# E22_TTL_RS232_v0_1_-20200417.net
KiCad netlist of a schematic drawn in Altium Designer
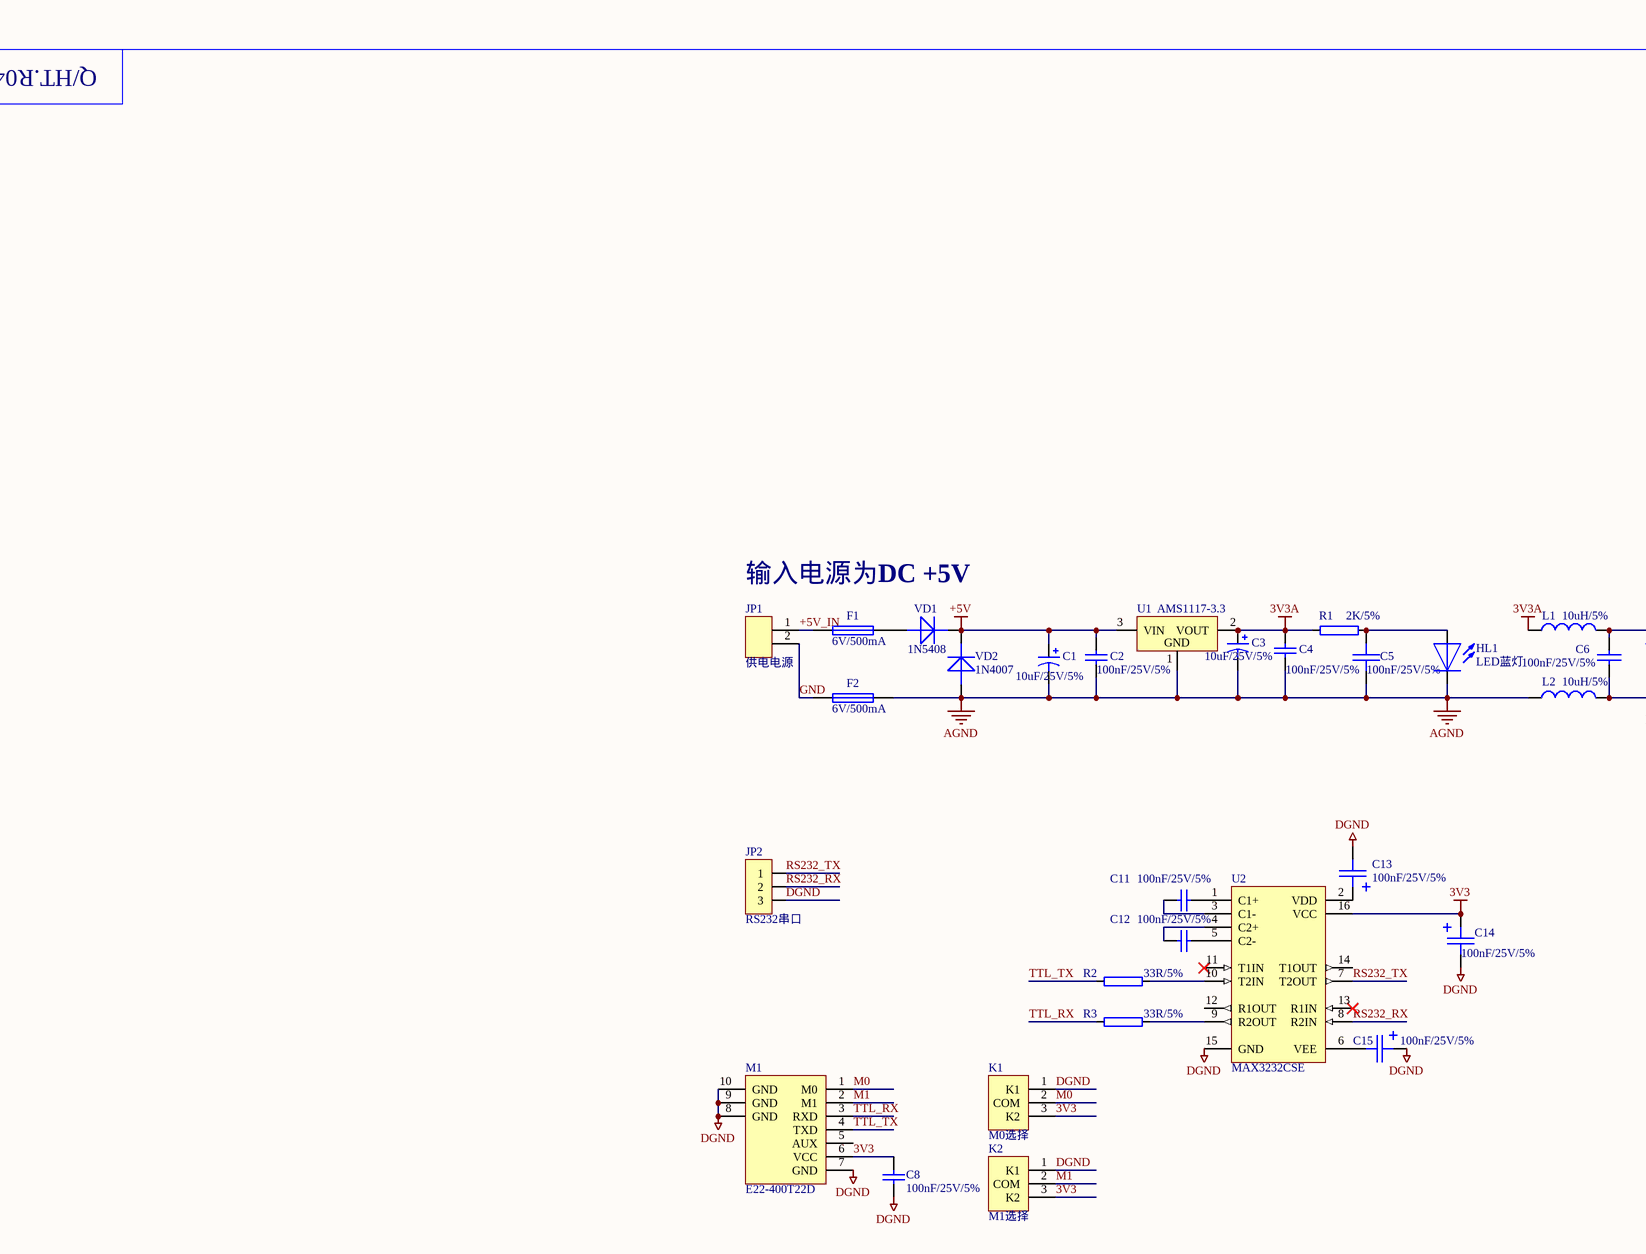
[diagram p0: E22_TTL_RS232(v0.1)-20200417.SchDoc, top left]
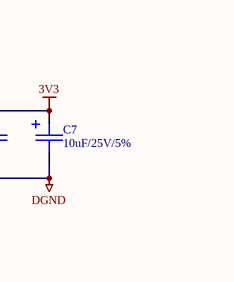
[diagram p1: E22_TTL_RS232(v0.1)-20200417.SchDoc, top right]
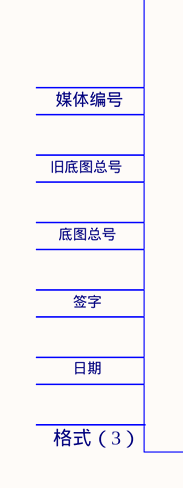
[diagram p2: E22_TTL_RS232(v0.1)-20200417.SchDoc, bottom left]
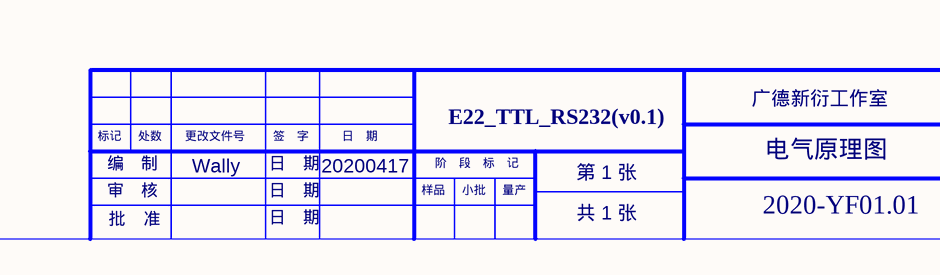
[diagram p3: E22_TTL_RS232(v0.1)-20200417.SchDoc, bottom right]

(export (version "E")
  (design (tool "Eeschema 10.0.6"))
  (components
    (comp (ref "C1")
      (value "10uF/25V/5%")
      (footprint "C1206-1")
      (description "钽电容")
      (fields (field (name "PUBLISHER") "Altium Limited"))
      (libsource (lib "Miscellaneous Devices") (part "Cap Pol1"))
    )
    (comp (ref "C2")
      (value "100nF/25V/5%")
      (footprint "C0603")
      (description "电容")
      (fields (field (name "PUBLISHER") "Altium Limited"))
      (libsource (lib "Miscellaneous Devices") (part "Cap"))
    )
    (comp (ref "C3")
      (value "10uF/25V/5%")
      (footprint "C1206-1")
      (description "钽电容")
      (fields (field (name "PUBLISHER") "Altium Limited"))
      (libsource (lib "Miscellaneous Devices") (part "Cap Pol1"))
    )
    (comp (ref "C4")
      (value "100nF/25V/5%")
      (footprint "C0603")
      (description "电容")
      (fields (field (name "PUBLISHER") "Altium Limited"))
      (libsource (lib "Miscellaneous Devices") (part "Cap"))
    )
    (comp (ref "C5")
      (value "100nF/25V/5%")
      (footprint "C0603")
      (description "电容")
      (libsource (lib "") (part "CAP_1"))
    )
    (comp (ref "C6")
      (value "100nF/25V/5%")
      (footprint "C0603")
      (description "电容")
      (libsource (lib "*") (part "CAP"))
    )
    (comp (ref "C7")
      (value "10uF/25V/5%")
      (footprint "C1206-1")
      (description "钽电容")
      (libsource (lib "*") (part "ELECTRO1"))
    )
    (comp (ref "C8")
      (value "100nF/25V/5%")
      (footprint "C0603")
      (description "电容")
      (libsource (lib "*") (part "CAP-SMD"))
    )
    (comp (ref "C11")
      (value "100nF/25V/5%")
      (footprint "C0603")
      (description "电容")
      (libsource (lib "*") (part "CAP-SMD"))
    )
    (comp (ref "C12")
      (value "100nF/25V/5%")
      (footprint "C0603")
      (description "电容")
      (libsource (lib "*") (part "CAP-SMD"))
    )
    (comp (ref "C13")
      (value "100nF/25V/5%")
      (footprint "C1206-1")
      (description "钽电容")
      (libsource (lib "*") (part "ELECTRO1"))
    )
    (comp (ref "C14")
      (value "100nF/25V/5%")
      (footprint "C1206-1")
      (description "钽电容")
      (libsource (lib "*") (part "ELECTRO1"))
    )
    (comp (ref "C15")
      (value "100nF/25V/5%")
      (footprint "C1206-1")
      (description "钽电容")
      (libsource (lib "*") (part "ELECTRO1"))
    )
    (comp (ref "F1")
      (value "6V/500mA")
      (footprint "F1812")
      (description "自恢复保险丝")
      (libsource (lib "wypPCB_Lib") (part "保险丝"))
    )
    (comp (ref "F2")
      (value "6V/500mA")
      (footprint "F1812")
      (description "自恢复保险丝")
      (libsource (lib "wypPCB_Lib") (part "保险丝"))
    )
    (comp (ref "HL1")
      (value "LED蓝灯")
      (footprint "LED0603")
      (description "发光二极管")
      (libsource (lib "wypPCB_Lib") (part "发光二极管"))
    )
    (comp (ref "JP1")
      (value "供电电源")
      (footprint "XH2.54-LI-2P")
      (description "XH2.54-2P/PH2.0-2P插座")
      (libsource (lib "wypPCB_Lib") (part "XH2.54-2P/PH2.0-2P"))
    )
    (comp (ref "JP2")
      (value "RS232串口")
      (footprint "PH2.0-LI-3P")
      (description "PH2.0-3P直插插座")
      (libsource (lib "wypPCB_Lib") (part "XH2.54-3P/PH2.0-3P"))
    )
    (comp (ref "K1")
      (value "M0选择")
      (footprint "SK-12D07")
      (description "SK-12D07：3脚2档小型拨动开关")
      (libsource (lib "wypPCB_Lib") (part "SK-12D07"))
    )
    (comp (ref "K2")
      (value "M1选择")
      (footprint "SK-12D07")
      (description "SK-12D07：3脚2档小型拨动开关")
      (libsource (lib "wypPCB_Lib") (part "SK-12D07"))
    )
    (comp (ref "L1")
      (value "10uH/5%")
      (footprint "L0603")
      (description "电感")
      (libsource (lib "wypPCB_Lib") (part "电感"))
    )
    (comp (ref "L2")
      (value "10uH/5%")
      (footprint "L0603")
      (description "电感")
      (libsource (lib "wypPCB_Lib") (part "电感"))
    )
    (comp (ref "M1")
      (value "E22-400T22D")
      (footprint "E22-400T22D")
      (description "E22-400T22D LoRa模块")
      (libsource (lib "wypPCB_Lib") (part "E22-400T22D"))
    )
    (comp (ref "R1")
      (value "2K/5%")
      (footprint "R0603")
      (description "电阻")
      (libsource (lib "*") (part "RES2"))
    )
    (comp (ref "R2")
      (value "33R/5%")
      (footprint "R0603")
      (description "电阻")
      (libsource (lib "*") (part "RES2"))
    )
    (comp (ref "R3")
      (value "33R/5%")
      (footprint "R0603")
      (description "电阻")
      (libsource (lib "*") (part "RES2"))
    )
    (comp (ref "U1")
      (value "AMS1117-3.3")
      (footprint "SOT230P700X180-4N")
      (description "U_AMS1117稳压芯片")
      (libsource (lib "wypPCB_Lib") (part "U_AMS1117"))
    )
    (comp (ref "U2")
      (value "MAX3232CSE")
      (footprint "NSO16_M")
      (description "+5V Powered, Multi-Channel RS-232 Driver/Receiver")
      (fields (field (name "PUBLISHER") "Altium Limited"))
      (libsource (lib "Maxim Communication Transceiver") (part "MAX232CSE"))
    )
    (comp (ref "VD1")
      (value "1N5408")
      (footprint "SMA_DO-214AC")
      (description "开关二极管")
      (libsource (lib "wypPCB_Lib") (part "开关二极管"))
    )
    (comp (ref "VD2")
      (value "1N4007")
      (footprint "SMA_DO-214AC")
      (description "开关二极管")
      (libsource (lib "wypPCB_Lib") (part "开关二极管"))
    )
  )
  (nets
    (net (code "1") (name "+5V") (class "Default")
      (node (ref "C1") (pin "1") (pinfunction "1_1") (pintype "passive"))
      (node (ref "C2") (pin "2") (pinfunction "2_2") (pintype "passive"))
      (node (ref "U1") (pin "3") (pinfunction "VIN_3") (pintype "passive"))
      (node (ref "VD1") (pin "K") (pintype "passive"))
      (node (ref "VD2") (pin "K") (pintype "passive"))
    )
    (net (code "2") (name "/+5V_IN") (class "Default")
      (node (ref "F1") (pin "1") (pintype "passive"))
      (node (ref "JP1") (pin "1") (pintype "passive"))
    )
    (net (code "3") (name "/GND") (class "Default")
      (node (ref "F2") (pin "1") (pintype "passive"))
      (node (ref "JP1") (pin "2") (pintype "passive"))
    )
    (net (code "4") (name "/M0") (class "Default")
      (node (ref "K1") (pin "2") (pinfunction "COM_2") (pintype "passive"))
      (node (ref "M1") (pin "1") (pinfunction "M0_1") (pintype "passive"))
    )
    (net (code "5") (name "/M1") (class "Default")
      (node (ref "K2") (pin "2") (pinfunction "COM_2") (pintype "passive"))
      (node (ref "M1") (pin "2") (pinfunction "M1_2") (pintype "passive"))
    )
    (net (code "6") (name "/RS232_RX") (class "Default")
      (node (ref "JP2") (pin "2") (pinfunction "2_2") (pintype "passive"))
      (node (ref "U2") (pin "8") (pinfunction "R2IN_8") (pintype "input"))
    )
    (net (code "7") (name "/RS232_TX") (class "Default")
      (node (ref "JP2") (pin "1") (pinfunction "1_1") (pintype "passive"))
      (node (ref "U2") (pin "7") (pinfunction "T2OUT_7") (pintype "output"))
    )
    (net (code "8") (name "/TTL_RX") (class "Default")
      (node (ref "M1") (pin "3") (pinfunction "RXD_3") (pintype "passive"))
      (node (ref "R3") (pin "2") (pintype "passive"))
    )
    (net (code "9") (name "/TTL_TX") (class "Default")
      (node (ref "M1") (pin "4") (pinfunction "TXD_4") (pintype "passive"))
      (node (ref "R2") (pin "2") (pintype "passive"))
    )
    (net (code "10") (name "3V3") (class "Default")
      (node (ref "C14") (pin "1") (pintype "passive"))
      (node (ref "C6") (pin "2") (pintype "passive"))
      (node (ref "C7") (pin "1") (pintype "passive"))
      (node (ref "C8") (pin "2") (pintype "passive"))
      (node (ref "K1") (pin "3") (pinfunction "K2_3") (pintype "passive"))
      (node (ref "K2") (pin "3") (pinfunction "K2_3") (pintype "passive"))
      (node (ref "L1") (pin "2") (pinfunction "2_2") (pintype "passive"))
      (node (ref "M1") (pin "6") (pinfunction "VCC_6") (pintype "passive"))
      (node (ref "U2") (pin "16") (pinfunction "VCC_16") (pintype "power_in"))
    )
    (net (code "11") (name "3V3A") (class "Default")
      (node (ref "C3") (pin "1") (pinfunction "1_1") (pintype "passive"))
      (node (ref "C4") (pin "2") (pinfunction "2_2") (pintype "passive"))
      (node (ref "L1") (pin "1") (pinfunction "1_1") (pintype "passive"))
      (node (ref "R1") (pin "1") (pintype "passive"))
      (node (ref "U1") (pin "2") (pinfunction "VOUT_2") (pintype "passive"))
    )
    (net (code "12") (name "AGND") (class "Default")
      (node (ref "C1") (pin "2") (pinfunction "2_2") (pintype "passive"))
      (node (ref "C2") (pin "1") (pinfunction "1_1") (pintype "passive"))
      (node (ref "C3") (pin "2") (pinfunction "2_2") (pintype "passive"))
      (node (ref "C4") (pin "1") (pinfunction "1_1") (pintype "passive"))
      (node (ref "C5") (pin "2") (pintype "passive"))
      (node (ref "F2") (pin "2") (pintype "passive"))
      (node (ref "HL1") (pin "K") (pintype "passive"))
      (node (ref "L2") (pin "1") (pinfunction "1_1") (pintype "passive"))
      (node (ref "U1") (pin "1") (pinfunction "GND_1") (pintype "passive"))
      (node (ref "VD2") (pin "A") (pintype "passive"))
    )
    (net (code "13") (name "DGND") (class "Default")
      (node (ref "C13") (pin "2") (pintype "passive"))
      (node (ref "C14") (pin "2") (pintype "passive"))
      (node (ref "C15") (pin "1") (pintype "passive"))
      (node (ref "C6") (pin "1") (pintype "passive"))
      (node (ref "C7") (pin "2") (pintype "passive"))
      (node (ref "C8") (pin "1") (pintype "passive"))
      (node (ref "JP2") (pin "3") (pinfunction "3_3") (pintype "passive"))
      (node (ref "K1") (pin "1") (pinfunction "K1_1") (pintype "passive"))
      (node (ref "K2") (pin "1") (pinfunction "K1_1") (pintype "passive"))
      (node (ref "L2") (pin "2") (pinfunction "2_2") (pintype "passive"))
      (node (ref "M1") (pin "10") (pinfunction "GND_10") (pintype "passive"))
      (node (ref "M1") (pin "7") (pinfunction "GND_7") (pintype "passive"))
      (node (ref "M1") (pin "8") (pinfunction "GND_8") (pintype "passive"))
      (node (ref "M1") (pin "9") (pinfunction "GND_9") (pintype "passive"))
      (node (ref "U2") (pin "15") (pinfunction "GND_15") (pintype "power_in"))
    )
    (net (code "14") (name "Net-(C5-Pad1)") (class "Default")
      (node (ref "C5") (pin "1") (pintype "passive"))
      (node (ref "HL1") (pin "A") (pintype "passive"))
      (node (ref "R1") (pin "2") (pintype "passive"))
    )
    (net (code "15") (name "Net-(F1-Pad2)") (class "Default")
      (node (ref "F1") (pin "2") (pintype "passive"))
      (node (ref "VD1") (pin "A") (pintype "passive"))
    )
    (net (code "16") (name "Net-(U2-C1+)") (class "Default")
      (node (ref "C11") (pin "2") (pintype "passive"))
      (node (ref "U2") (pin "1") (pinfunction "C1+_1") (pintype "passive"))
    )
    (net (code "17") (name "Net-(U2-C1-)") (class "Default")
      (node (ref "C11") (pin "1") (pintype "passive"))
      (node (ref "U2") (pin "3") (pinfunction "C1-_3") (pintype "passive"))
    )
    (net (code "18") (name "Net-(U2-C2+)") (class "Default")
      (node (ref "C12") (pin "1") (pintype "passive"))
      (node (ref "U2") (pin "4") (pinfunction "C2+_4") (pintype "passive"))
    )
    (net (code "19") (name "Net-(U2-C2-)") (class "Default")
      (node (ref "C12") (pin "2") (pintype "passive"))
      (node (ref "U2") (pin "5") (pinfunction "C2-_5") (pintype "passive"))
    )
    (net (code "20") (name "Net-(U2-R2OUT)") (class "Default")
      (node (ref "R3") (pin "1") (pintype "passive"))
      (node (ref "U2") (pin "9") (pinfunction "R2OUT_9") (pintype "output"))
    )
    (net (code "21") (name "Net-(U2-T2IN)") (class "Default")
      (node (ref "R2") (pin "1") (pintype "passive"))
      (node (ref "U2") (pin "10") (pinfunction "T2IN_10") (pintype "input"))
    )
    (net (code "22") (name "Net-(U2-VDD)") (class "Default")
      (node (ref "C13") (pin "1") (pintype "passive"))
      (node (ref "U2") (pin "2") (pinfunction "VDD_2") (pintype "power_in"))
    )
    (net (code "23") (name "Net-(U2-VEE)") (class "Default")
      (node (ref "C15") (pin "2") (pintype "passive"))
      (node (ref "U2") (pin "6") (pinfunction "VEE_6") (pintype "power_in"))
    )
    (net (code "24") (name "unconnected-(M1-AUX-Pad5)") (class "Default")
      (node (ref "M1") (pin "5") (pinfunction "AUX_5") (pintype "passive"))
    )
    (net (code "25") (name "unconnected-(U2-R1IN-Pad13)") (class "Default")
      (node (ref "U2") (pin "13") (pinfunction "R1IN_13") (pintype "input+no_connect"))
    )
    (net (code "26") (name "unconnected-(U2-R1OUT-Pad12)") (class "Default")
      (node (ref "U2") (pin "12") (pinfunction "R1OUT_12") (pintype "output"))
    )
    (net (code "27") (name "unconnected-(U2-T1IN-Pad11)") (class "Default")
      (node (ref "U2") (pin "11") (pinfunction "T1IN_11") (pintype "input+no_connect"))
    )
    (net (code "28") (name "unconnected-(U2-T1OUT-Pad14)") (class "Default")
      (node (ref "U2") (pin "14") (pinfunction "T1OUT_14") (pintype "output"))
    )
  )
)
